# 02.net
KiCad netlist of a schematic drawn in Altium Designer
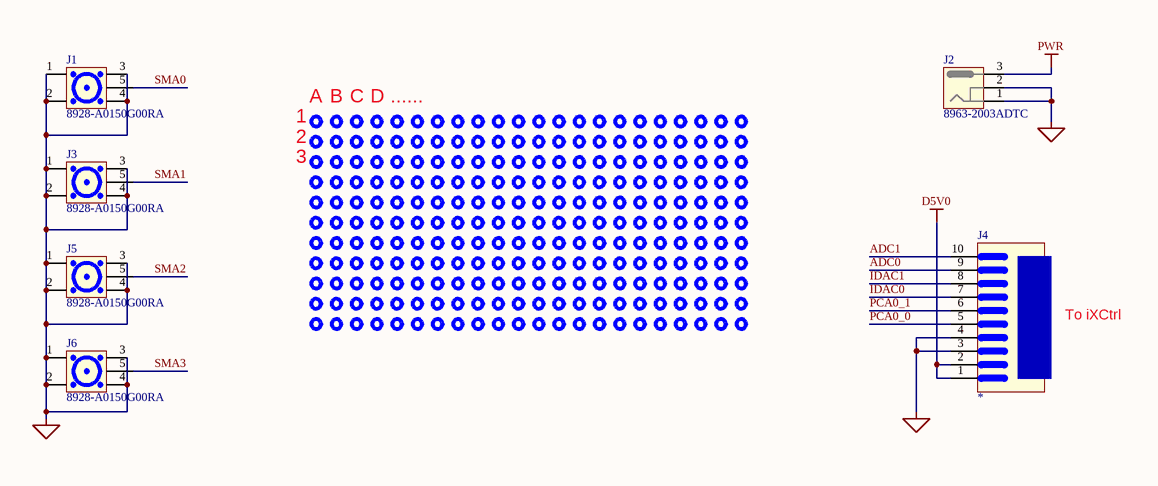
[diagram p0: 02.SchDoc]

(export (version "E")
  (design (tool "Eeschema 10.0.6"))
  (components
    (comp (ref "J1")
      (value "8928-A0150G00RA")
      (footprint "8928-A0150G00RA")
      (description "SMA,female,50ohm,right angle,TH")
      (libsource (lib "AD15_schlib") (part "8928-A0150"))
    )
    (comp (ref "J2")
      (value "8963-2003ADTC")
      (footprint "8963-2003ADTC")
      (description "DC jack,2.0mm,SMD")
      (libsource (lib "AD15_schlib") (part "8963-2003"))
    )
    (comp (ref "J3")
      (value "8928-A0150G00RA")
      (footprint "8928-A0150G00RA")
      (description "SMA,female,50ohm,right angle,TH")
      (libsource (lib "AD15_schlib") (part "8928-A0150"))
    )
    (comp (ref "J4")
      (value "*")
      (footprint "FPC0.5mm-10pin")
      (description "FFC socket,10-Pin,bottom contact,0.5mm Pitch,SMD")
      (libsource (lib "AD15_schlib") (part "FPC0.5mm_06"))
    )
    (comp (ref "J5")
      (value "8928-A0150G00RA")
      (footprint "8928-A0150G00RA")
      (description "SMA,female,50ohm,right angle,TH")
      (libsource (lib "AD15_schlib") (part "8928-A0150"))
    )
    (comp (ref "J6")
      (value "8928-A0150G00RA")
      (footprint "8928-A0150G00RA")
      (description "SMA,female,50ohm,right angle,TH")
      (libsource (lib "AD15_schlib") (part "8928-A0150"))
    )
  )
  (nets
    (net (code "1") (name "/ADC0") (class "Default")
      (node (ref "J4") (pin "9") (pinfunction "8_9") (pintype "passive"))
    )
    (net (code "2") (name "/ADC1") (class "Default")
      (node (ref "J4") (pin "10") (pinfunction "9_10") (pintype "passive"))
    )
    (net (code "3") (name "/IDAC0") (class "Default")
      (node (ref "J4") (pin "7") (pinfunction "6_7") (pintype "passive"))
    )
    (net (code "4") (name "/IDAC1") (class "Default")
      (node (ref "J4") (pin "8") (pinfunction "7_8") (pintype "passive"))
    )
    (net (code "5") (name "/PCA0_0") (class "Default")
      (node (ref "J4") (pin "5") (pinfunction "4_5") (pintype "passive"))
    )
    (net (code "6") (name "/PCA0_1") (class "Default")
      (node (ref "J4") (pin "6") (pinfunction "5_6") (pintype "passive"))
    )
    (net (code "7") (name "/SMA0") (class "Default") (node (ref "J1") (pin "5") (pintype "passive")))
    (net (code "8") (name "/SMA1") (class "Default") (node (ref "J3") (pin "5") (pintype "passive")))
    (net (code "9") (name "/SMA2") (class "Default") (node (ref "J5") (pin "5") (pintype "passive")))
    (net (code "10") (name "/SMA3") (class "Default") (node (ref "J6") (pin "5") (pintype "passive")))
    (net (code "11") (name "D5V0") (class "Default")
      (node (ref "J4") (pin "1") (pinfunction "0_1") (pintype "passive"))
      (node (ref "J4") (pin "2") (pinfunction "1_2") (pintype "passive"))
    )
    (net (code "12") (name "GND") (class "Default")
      (node (ref "J1") (pin "1") (pintype "passive"))
      (node (ref "J1") (pin "2") (pintype "passive"))
      (node (ref "J1") (pin "3") (pintype "passive"))
      (node (ref "J1") (pin "4") (pintype "passive"))
      (node (ref "J2") (pin "1") (pintype "passive"))
      (node (ref "J2") (pin "2") (pintype "passive"))
      (node (ref "J3") (pin "1") (pintype "passive"))
      (node (ref "J3") (pin "2") (pintype "passive"))
      (node (ref "J3") (pin "3") (pintype "passive"))
      (node (ref "J3") (pin "4") (pintype "passive"))
      (node (ref "J4") (pin "3") (pinfunction "2_3") (pintype "passive"))
      (node (ref "J4") (pin "4") (pinfunction "3_4") (pintype "passive"))
      (node (ref "J5") (pin "1") (pintype "passive"))
      (node (ref "J5") (pin "2") (pintype "passive"))
      (node (ref "J5") (pin "3") (pintype "passive"))
      (node (ref "J5") (pin "4") (pintype "passive"))
      (node (ref "J6") (pin "1") (pintype "passive"))
      (node (ref "J6") (pin "2") (pintype "passive"))
      (node (ref "J6") (pin "3") (pintype "passive"))
      (node (ref "J6") (pin "4") (pintype "passive"))
    )
    (net (code "13") (name "PWR") (class "Default") (node (ref "J2") (pin "3") (pintype "passive")))
  )
)
